# PiPico.net
KiCad netlist of a schematic drawn in Altium Designer
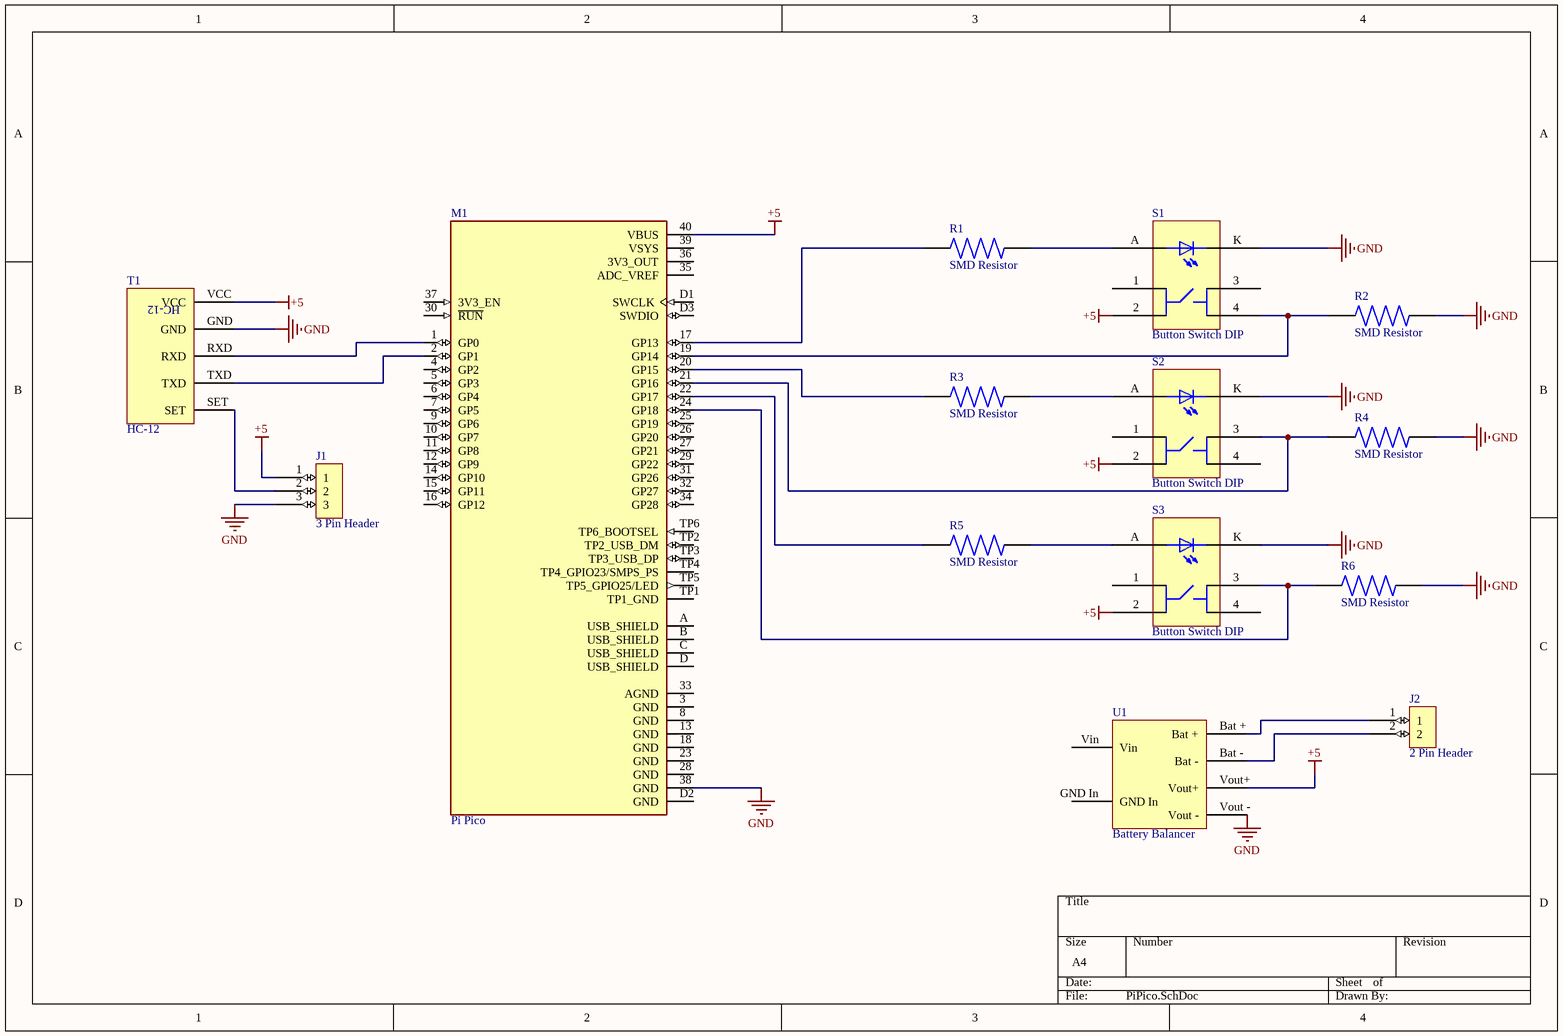
[diagram p0: PiPico.SchDoc]

(export (version "E")
  (design (tool "Eeschema 10.0.6"))
  (components
    (comp (ref "J1")
      (value "3 Pin Header")
      (footprint "3 Pin Header-Footprint-1")
      (description "3 Pin Breakout Header")
      (libsource (lib "Tobias") (part "3 Pin Header-Symbol-1"))
    )
    (comp (ref "J2")
      (value "2 Pin Header")
      (footprint "2 Pin Header-Footprint-1")
      (description "2Pin  Breakout Header")
      (libsource (lib "Tobias") (part "2 Pin Header-Symbol-1"))
    )
    (comp (ref "M1")
      (value "Pi Pico")
      (footprint "Pi Pico-Footprint-1")
      (libsource (lib "Tobias") (part "Pi Pico-Symbol-1"))
    )
    (comp (ref "R1")
      (value "SMD Resistor")
      (footprint "SMD Resistor-Footprint-1")
      (description "Generic SMD Resistor")
      (libsource (lib "Tobias") (part "SMD Resistor-Symbol-1"))
    )
    (comp (ref "R2")
      (value "SMD Resistor")
      (footprint "SMD Resistor-Footprint-1")
      (description "Generic SMD Resistor")
      (libsource (lib "Tobias") (part "SMD Resistor-Symbol-1"))
    )
    (comp (ref "R3")
      (value "SMD Resistor")
      (footprint "SMD Resistor-Footprint-1")
      (description "Generic SMD Resistor")
      (libsource (lib "Tobias") (part "SMD Resistor-Symbol-1"))
    )
    (comp (ref "R4")
      (value "SMD Resistor")
      (footprint "SMD Resistor-Footprint-1")
      (description "Generic SMD Resistor")
      (libsource (lib "Tobias") (part "SMD Resistor-Symbol-1"))
    )
    (comp (ref "R5")
      (value "SMD Resistor")
      (footprint "SMD Resistor-Footprint-1")
      (description "Generic SMD Resistor")
      (libsource (lib "Tobias") (part "SMD Resistor-Symbol-1"))
    )
    (comp (ref "R6")
      (value "SMD Resistor")
      (footprint "SMD Resistor-Footprint-1")
      (description "Generic SMD Resistor")
      (libsource (lib "Tobias") (part "SMD Resistor-Symbol-1"))
    )
    (comp (ref "S1")
      (value "Button Switch DIP")
      (footprint "Button Switch DIP -Footprint-1")
      (description "6 Pin with LED")
      (libsource (lib "Tobias") (part "Button Switch DIP -Symbol-1"))
    )
    (comp (ref "S2")
      (value "Button Switch DIP")
      (footprint "Button Switch DIP -Footprint-1")
      (description "6 Pin with LED")
      (libsource (lib "Tobias") (part "Button Switch DIP -Symbol-1"))
    )
    (comp (ref "S3")
      (value "Button Switch DIP")
      (footprint "Button Switch DIP -Footprint-1")
      (description "6 Pin with LED")
      (libsource (lib "Tobias") (part "Button Switch DIP -Symbol-1"))
    )
    (comp (ref "T1")
      (value "HC-12")
      (footprint "HC-12-Footprint-1")
      (description "UART Telemetry Antenna")
      (libsource (lib "Tobias") (part "HC-12-Symbol-1"))
    )
    (comp (ref "U1")
      (value "Battery Balancer")
      (footprint "Battery Balancer-Footprint-1")
      (description "1Cell LiPo Battery Module")
      (libsource (lib "Tobias") (part "Battery Balancer-Symbol-1"))
    )
  )
  (nets
    (net (code "1") (name "+5") (class "Default")
      (node (ref "J1") (pin "1") (pinfunction "1_1") (pintype "bidirectional"))
      (node (ref "M1") (pin "40") (pinfunction "VBUS_40") (pintype "power_in"))
      (node (ref "S1") (pin "2") (pinfunction "2_2") (pintype "passive"))
      (node (ref "S2") (pin "2") (pinfunction "2_2") (pintype "passive"))
      (node (ref "S3") (pin "2") (pinfunction "2_2") (pintype "passive"))
      (node (ref "T1") (pin "VCC") (pinfunction "VCC_VCC") (pintype "passive"))
      (node (ref "U1") (pin "Vout+") (pinfunction "Vout+_Vout+") (pintype "passive"))
    )
    (net (code "2") (name "GND") (class "Default")
      (node (ref "J1") (pin "3") (pinfunction "3_3") (pintype "bidirectional"))
      (node (ref "M1") (pin "38") (pinfunction "GND_38") (pintype "power_in"))
      (node (ref "R2") (pin "2") (pinfunction "2_2") (pintype "passive"))
      (node (ref "R4") (pin "2") (pinfunction "2_2") (pintype "passive"))
      (node (ref "R6") (pin "2") (pinfunction "2_2") (pintype "passive"))
      (node (ref "S1") (pin "K") (pinfunction "K_K") (pintype "passive"))
      (node (ref "S2") (pin "K") (pinfunction "K_K") (pintype "passive"))
      (node (ref "S3") (pin "K") (pinfunction "K_K") (pintype "passive"))
      (node (ref "T1") (pin "GND") (pinfunction "GND_GND") (pintype "passive"))
      (node (ref "U1") (pin "Vout_-") (pinfunction "Vout_-_Vout_-") (pintype "passive"))
    )
    (net (code "3") (name "Net-(J1-Pad2)") (class "Default")
      (node (ref "J1") (pin "2") (pinfunction "2_2") (pintype "bidirectional"))
      (node (ref "T1") (pin "SET") (pinfunction "SET_SET") (pintype "passive"))
    )
    (net (code "4") (name "Net-(J2-Pad1)") (class "Default")
      (node (ref "J2") (pin "1") (pinfunction "1_1") (pintype "bidirectional"))
      (node (ref "U1") (pin "Bat_+") (pinfunction "Bat_+_Bat_+") (pintype "passive"))
    )
    (net (code "5") (name "Net-(J2-Pad2)") (class "Default")
      (node (ref "J2") (pin "2") (pinfunction "2_2") (pintype "bidirectional"))
      (node (ref "U1") (pin "Bat_-") (pinfunction "Bat_-_Bat_-") (pintype "passive"))
    )
    (net (code "6") (name "Net-(M1-GP0)") (class "Default")
      (node (ref "M1") (pin "1") (pinfunction "GP0_1") (pintype "bidirectional"))
      (node (ref "T1") (pin "RXD") (pinfunction "RXD_RXD") (pintype "passive"))
    )
    (net (code "7") (name "Net-(M1-GP1)") (class "Default")
      (node (ref "M1") (pin "2") (pinfunction "GP1_2") (pintype "bidirectional"))
      (node (ref "T1") (pin "TXD") (pinfunction "TXD_TXD") (pintype "passive"))
    )
    (net (code "8") (name "Net-(M1-GP13)") (class "Default")
      (node (ref "M1") (pin "17") (pinfunction "GP13_17") (pintype "bidirectional"))
      (node (ref "R1") (pin "1") (pinfunction "1_1") (pintype "passive"))
    )
    (net (code "9") (name "Net-(M1-GP14)") (class "Default")
      (node (ref "M1") (pin "19") (pinfunction "GP14_19") (pintype "bidirectional"))
      (node (ref "R2") (pin "1") (pinfunction "1_1") (pintype "passive"))
      (node (ref "S1") (pin "4") (pinfunction "4_4") (pintype "passive"))
    )
    (net (code "10") (name "Net-(M1-GP15)") (class "Default")
      (node (ref "M1") (pin "20") (pinfunction "GP15_20") (pintype "bidirectional"))
      (node (ref "R3") (pin "1") (pinfunction "1_1") (pintype "passive"))
    )
    (net (code "11") (name "Net-(M1-GP16)") (class "Default")
      (node (ref "M1") (pin "21") (pinfunction "GP16_21") (pintype "bidirectional"))
      (node (ref "R4") (pin "1") (pinfunction "1_1") (pintype "passive"))
      (node (ref "S2") (pin "3") (pinfunction "3_3") (pintype "passive"))
    )
    (net (code "12") (name "Net-(M1-GP17)") (class "Default")
      (node (ref "M1") (pin "22") (pinfunction "GP17_22") (pintype "bidirectional"))
      (node (ref "R5") (pin "1") (pinfunction "1_1") (pintype "passive"))
    )
    (net (code "13") (name "Net-(M1-GP18)") (class "Default")
      (node (ref "M1") (pin "24") (pinfunction "GP18_24") (pintype "bidirectional"))
      (node (ref "R6") (pin "1") (pinfunction "1_1") (pintype "passive"))
      (node (ref "S3") (pin "3") (pinfunction "3_3") (pintype "passive"))
    )
    (net (code "14") (name "Net-(R1-Pad2)") (class "Default")
      (node (ref "R1") (pin "2") (pinfunction "2_2") (pintype "passive"))
      (node (ref "S1") (pin "A") (pinfunction "A_A") (pintype "passive"))
    )
    (net (code "15") (name "Net-(R3-Pad2)") (class "Default")
      (node (ref "R3") (pin "2") (pinfunction "2_2") (pintype "passive"))
      (node (ref "S2") (pin "A") (pinfunction "A_A") (pintype "passive"))
    )
    (net (code "16") (name "Net-(R5-Pad2)") (class "Default")
      (node (ref "R5") (pin "2") (pinfunction "2_2") (pintype "passive"))
      (node (ref "S3") (pin "A") (pinfunction "A_A") (pintype "passive"))
    )
    (net (code "17") (name "unconnected-(M1-3V3_EN-Pad37)") (class "Default")
      (node (ref "M1") (pin "37") (pinfunction "3V3_EN_37") (pintype "input"))
    )
    (net (code "18") (name "unconnected-(M1-3V3_OUT-Pad36)") (class "Default")
      (node (ref "M1") (pin "36") (pinfunction "3V3_OUT_36") (pintype "power_in"))
    )
    (net (code "19") (name "unconnected-(M1-ADC_VREF-Pad35)") (class "Default")
      (node (ref "M1") (pin "35") (pinfunction "ADC_VREF_35") (pintype "power_in"))
    )
    (net (code "20") (name "unconnected-(M1-AGND-Pad33)") (class "Default")
      (node (ref "M1") (pin "33") (pinfunction "AGND_33") (pintype "power_in"))
    )
    (net (code "21") (name "unconnected-(M1-GND-Pad3)") (class "Default")
      (node (ref "M1") (pin "3") (pinfunction "GND_3") (pintype "power_in"))
    )
    (net (code "22") (name "unconnected-(M1-GND-Pad8)") (class "Default")
      (node (ref "M1") (pin "8") (pinfunction "GND_8") (pintype "power_in"))
    )
    (net (code "23") (name "unconnected-(M1-GND-Pad13)") (class "Default")
      (node (ref "M1") (pin "13") (pinfunction "GND_13") (pintype "power_in"))
    )
    (net (code "24") (name "unconnected-(M1-GND-Pad18)") (class "Default")
      (node (ref "M1") (pin "18") (pinfunction "GND_18") (pintype "power_in"))
    )
    (net (code "25") (name "unconnected-(M1-GND-Pad23)") (class "Default")
      (node (ref "M1") (pin "23") (pinfunction "GND_23") (pintype "power_in"))
    )
    (net (code "26") (name "unconnected-(M1-GND-Pad28)") (class "Default")
      (node (ref "M1") (pin "28") (pinfunction "GND_28") (pintype "power_in"))
    )
    (net (code "27") (name "unconnected-(M1-GND-PadD2)") (class "Default")
      (node (ref "M1") (pin "D2") (pinfunction "GND_D2") (pintype "power_in"))
    )
    (net (code "28") (name "unconnected-(M1-GP2-Pad4)") (class "Default")
      (node (ref "M1") (pin "4") (pinfunction "GP2_4") (pintype "bidirectional"))
    )
    (net (code "29") (name "unconnected-(M1-GP3-Pad5)") (class "Default")
      (node (ref "M1") (pin "5") (pinfunction "GP3_5") (pintype "bidirectional"))
    )
    (net (code "30") (name "unconnected-(M1-GP4-Pad6)") (class "Default")
      (node (ref "M1") (pin "6") (pinfunction "GP4_6") (pintype "bidirectional"))
    )
    (net (code "31") (name "unconnected-(M1-GP5-Pad7)") (class "Default")
      (node (ref "M1") (pin "7") (pinfunction "GP5_7") (pintype "bidirectional"))
    )
    (net (code "32") (name "unconnected-(M1-GP6-Pad9)") (class "Default")
      (node (ref "M1") (pin "9") (pinfunction "GP6_9") (pintype "bidirectional"))
    )
    (net (code "33") (name "unconnected-(M1-GP7-Pad10)") (class "Default")
      (node (ref "M1") (pin "10") (pinfunction "GP7_10") (pintype "bidirectional"))
    )
    (net (code "34") (name "unconnected-(M1-GP8-Pad11)") (class "Default")
      (node (ref "M1") (pin "11") (pinfunction "GP8_11") (pintype "bidirectional"))
    )
    (net (code "35") (name "unconnected-(M1-GP9-Pad12)") (class "Default")
      (node (ref "M1") (pin "12") (pinfunction "GP9_12") (pintype "bidirectional"))
    )
    (net (code "36") (name "unconnected-(M1-GP10-Pad14)") (class "Default")
      (node (ref "M1") (pin "14") (pinfunction "GP10_14") (pintype "bidirectional"))
    )
    (net (code "37") (name "unconnected-(M1-GP11-Pad15)") (class "Default")
      (node (ref "M1") (pin "15") (pinfunction "GP11_15") (pintype "bidirectional"))
    )
    (net (code "38") (name "unconnected-(M1-GP12-Pad16)") (class "Default")
      (node (ref "M1") (pin "16") (pinfunction "GP12_16") (pintype "bidirectional"))
    )
    (net (code "39") (name "unconnected-(M1-GP19-Pad25)") (class "Default")
      (node (ref "M1") (pin "25") (pinfunction "GP19_25") (pintype "bidirectional"))
    )
    (net (code "40") (name "unconnected-(M1-GP20-Pad26)") (class "Default")
      (node (ref "M1") (pin "26") (pinfunction "GP20_26") (pintype "bidirectional"))
    )
    (net (code "41") (name "unconnected-(M1-GP21-Pad27)") (class "Default")
      (node (ref "M1") (pin "27") (pinfunction "GP21_27") (pintype "bidirectional"))
    )
    (net (code "42") (name "unconnected-(M1-GP22-Pad29)") (class "Default")
      (node (ref "M1") (pin "29") (pinfunction "GP22_29") (pintype "bidirectional"))
    )
    (net (code "43") (name "unconnected-(M1-GP26-Pad31)") (class "Default")
      (node (ref "M1") (pin "31") (pinfunction "GP26_31") (pintype "bidirectional"))
    )
    (net (code "44") (name "unconnected-(M1-GP27-Pad32)") (class "Default")
      (node (ref "M1") (pin "32") (pinfunction "GP27_32") (pintype "bidirectional"))
    )
    (net (code "45") (name "unconnected-(M1-GP28-Pad34)") (class "Default")
      (node (ref "M1") (pin "34") (pinfunction "GP28_34") (pintype "bidirectional"))
    )
    (net (code "46") (name "unconnected-(M1-SWCLK-PadD1)") (class "Default")
      (node (ref "M1") (pin "D1") (pinfunction "SWCLK_D1") (pintype "input"))
    )
    (net (code "47") (name "unconnected-(M1-SWDIO-PadD3)") (class "Default")
      (node (ref "M1") (pin "D3") (pinfunction "SWDIO_D3") (pintype "bidirectional"))
    )
    (net (code "48") (name "unconnected-(M1-TP1_GND-PadTP1)") (class "Default")
      (node (ref "M1") (pin "TP1") (pinfunction "TP1_GND_TP1") (pintype "power_in"))
    )
    (net (code "49") (name "unconnected-(M1-TP2_USB_DM-PadTP2)") (class "Default")
      (node (ref "M1") (pin "TP2") (pinfunction "TP2_USB_DM_TP2") (pintype "bidirectional"))
    )
    (net (code "50") (name "unconnected-(M1-TP3_USB_DP-PadTP3)") (class "Default")
      (node (ref "M1") (pin "TP3") (pinfunction "TP3_USB_DP_TP3") (pintype "bidirectional"))
    )
    (net (code "51") (name "unconnected-(M1-TP4_GPIO23{slash}SMPS_PS-PadTP4)") (class "Default")
      (node (ref "M1") (pin "TP4") (pinfunction "TP4_GPIO23/SMPS_PS_TP4") (pintype "passive"))
    )
    (net (code "52") (name "unconnected-(M1-TP5_GPIO25{slash}LED-PadTP5)") (class "Default")
      (node (ref "M1") (pin "TP5") (pinfunction "TP5_GPIO25/LED_TP5") (pintype "output"))
    )
    (net (code "53") (name "unconnected-(M1-TP6_BOOTSEL-PadTP6)") (class "Default")
      (node (ref "M1") (pin "TP6") (pinfunction "TP6_BOOTSEL_TP6") (pintype "input"))
    )
    (net (code "54") (name "unconnected-(M1-USB_SHIELD-PadA)") (class "Default")
      (node (ref "M1") (pin "A") (pinfunction "USB_SHIELD_A") (pintype "power_in"))
    )
    (net (code "55") (name "unconnected-(M1-USB_SHIELD-PadB)") (class "Default")
      (node (ref "M1") (pin "B") (pinfunction "USB_SHIELD_B") (pintype "power_in"))
    )
    (net (code "56") (name "unconnected-(M1-USB_SHIELD-PadC)") (class "Default")
      (node (ref "M1") (pin "C") (pinfunction "USB_SHIELD_C") (pintype "power_in"))
    )
    (net (code "57") (name "unconnected-(M1-USB_SHIELD-PadD)") (class "Default")
      (node (ref "M1") (pin "D") (pinfunction "USB_SHIELD_D") (pintype "power_in"))
    )
    (net (code "58") (name "unconnected-(M1-VSYS-Pad39)") (class "Default")
      (node (ref "M1") (pin "39") (pinfunction "VSYS_39") (pintype "power_in"))
    )
    (net (code "59") (name "unconnected-(M1-~{RUN}-Pad30)") (class "Default")
      (node (ref "M1") (pin "30") (pinfunction "~{RUN}_30") (pintype "input"))
    )
    (net (code "60") (name "unconnected-(S1-Pad1)") (class "Default")
      (node (ref "S1") (pin "1") (pinfunction "1_1") (pintype "passive"))
    )
    (net (code "61") (name "unconnected-(S1-Pad3)") (class "Default")
      (node (ref "S1") (pin "3") (pinfunction "3_3") (pintype "passive"))
    )
    (net (code "62") (name "unconnected-(S2-Pad1)") (class "Default")
      (node (ref "S2") (pin "1") (pinfunction "1_1") (pintype "passive"))
    )
    (net (code "63") (name "unconnected-(S2-Pad4)") (class "Default")
      (node (ref "S2") (pin "4") (pinfunction "4_4") (pintype "passive"))
    )
    (net (code "64") (name "unconnected-(S3-Pad1)") (class "Default")
      (node (ref "S3") (pin "1") (pinfunction "1_1") (pintype "passive"))
    )
    (net (code "65") (name "unconnected-(S3-Pad4)") (class "Default")
      (node (ref "S3") (pin "4") (pinfunction "4_4") (pintype "passive"))
    )
    (net (code "66") (name "unconnected-(U1-PadGND_In)") (class "Default")
      (node (ref "U1") (pin "GND_In") (pinfunction "GND_In_GND_In") (pintype "passive"))
    )
    (net (code "67") (name "unconnected-(U1-PadVin)") (class "Default")
      (node (ref "U1") (pin "Vin") (pinfunction "Vin_Vin") (pintype "passive"))
    )
  )
)
